# Barometer_revb.net
KiCad netlist of a schematic drawn in EAGLE
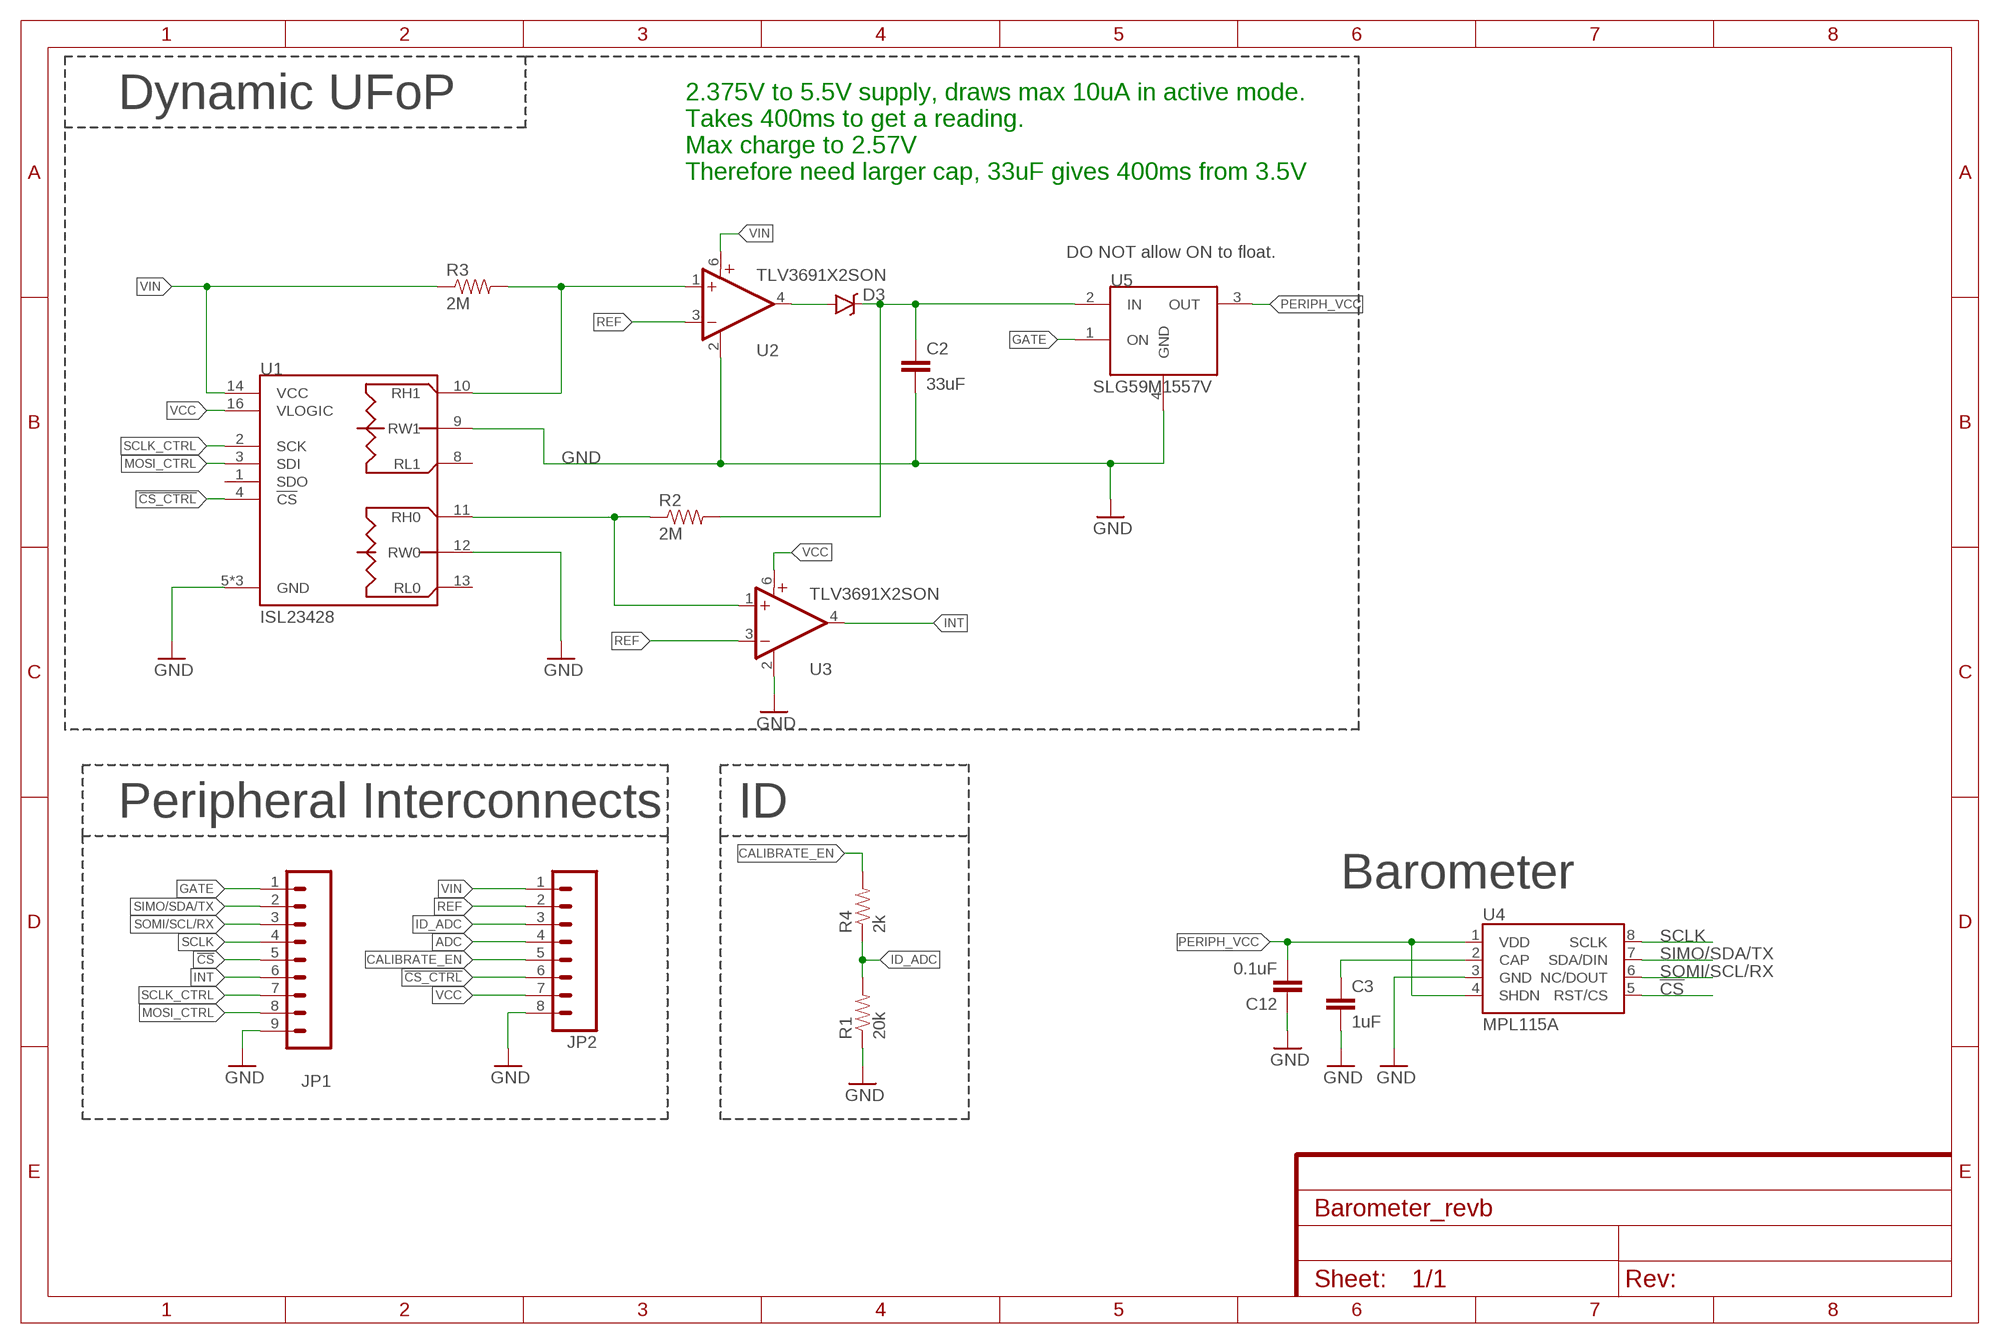
[diagram p0: schematic, sheet 1]

(export (version "E")
  (design (tool "Eeschema 10.0.6"))
  (components
    (comp (ref "C2")
      (value "33uF")
      (footprint "eagle-import:1206")
      (fields (field (name "MPN") "C3216X5R0J336M130AC "))
      (libsource (lib "eagle-import") (part "CAP1206"))
    )
    (comp (ref "C3")
      (value "1uF")
      (footprint "eagle-import:0402")
      (fields (field (name "MPN") "0402ZD105KAT2A"))
      (libsource (lib "eagle-import") (part "C-EU"))
    )
    (comp (ref "C12")
      (value "0.1uF")
      (footprint "eagle-import:0402")
      (fields (field (name "MPN") "0402YD104KAT2A"))
      (libsource (lib "eagle-import") (part "C-EU"))
    )
    (comp (ref "D3")
      (value "RB751")
      (footprint "eagle-import:SOD-523")
      (fields (field (name "MPN") "BAS40-02V-V-G-08"))
      (libsource (lib "eagle-import") (part "DIODE-SCHOTTKY-RB751"))
    )
    (comp (ref "JP1")
      (value "M091.27MM")
      (footprint "eagle-import:1X09-1.27MM")
      (fields (field (name "MPN") "GRPB091VWVN-RC "))
      (libsource (lib "eagle-import") (part "M091.27MM"))
    )
    (comp (ref "JP2")
      (value "M081.27MM")
      (footprint "eagle-import:1X08-1.27MM")
      (fields (field (name "MPN") "GRPB081VWVN-RC "))
      (libsource (lib "eagle-import") (part "M081.27MM"))
    )
    (comp (ref "R1")
      (value "20k")
      (footprint "eagle-import:0402")
      (fields (field (name "MPN") "ERJ-2RKF2002X"))
      (libsource (lib "eagle-import") (part "R-EU"))
    )
    (comp (ref "R2")
      (value "2M")
      (footprint "eagle-import:0402")
      (fields (field (name "MPN") "RC1005F205CS"))
      (libsource (lib "eagle-import") (part "R-EU"))
    )
    (comp (ref "R3")
      (value "2M")
      (footprint "eagle-import:0402")
      (fields (field (name "MPN") "RC1005F205CS"))
      (libsource (lib "eagle-import") (part "R-EU"))
    )
    (comp (ref "R4")
      (value "2k")
      (footprint "eagle-import:0402")
      (fields (field (name "MPN") "MCR01MRTF1202"))
      (libsource (lib "eagle-import") (part "R-EU"))
    )
    (comp (ref "U1")
      (value "ISL23428")
      (footprint "eagle-import:UTQFN-16")
      (fields (field (name "MPN") "ISL23428TFRUZ-T7A"))
      (libsource (lib "eagle-import") (part "ISL23428"))
    )
    (comp (ref "U2")
      (value "TLV3691X2SON")
      (footprint "eagle-import:X2SON")
      (fields (field (name "MPN") "TLV3691IDPFR"))
      (libsource (lib "eagle-import") (part "TLV3691X2SON"))
    )
    (comp (ref "U3")
      (value "TLV3691X2SON")
      (footprint "eagle-import:X2SON")
      (fields (field (name "MPN") "TLV3691IDPFR"))
      (libsource (lib "eagle-import") (part "TLV3691X2SON"))
    )
    (comp (ref "U4")
      (value "MPL115A")
      (footprint "eagle-import:LGA8")
      (fields (field (name "MPN") "MPL115A1"))
      (libsource (lib "eagle-import") (part "MPL115A"))
    )
    (comp (ref "U5")
      (value "SLG59M1557V")
      (footprint "eagle-import:4STDFN")
      (fields (field (name "MPN") "SLG59M1557V "))
      (libsource (lib "eagle-import") (part "SLG59M1557V"))
    )
  )
  (nets
    (net (code "1") (name "/~{CS_CTRL}") (class "Default")
      (node (ref "JP2") (pin "6") (pinfunction "6_6") (pintype "passive"))
      (node (ref "U1") (pin "4") (pinfunction "~{CS}_4") (pintype "bidirectional"))
    )
    (net (code "2") (name "/~{CS}") (class "Default")
      (node (ref "JP1") (pin "5") (pinfunction "5_5") (pintype "passive"))
      (node (ref "U4") (pin "5") (pinfunction "RST/CS_5") (pintype "bidirectional"))
    )
    (net (code "3") (name "ADC") (class "Default")
      (node (ref "JP2") (pin "4") (pinfunction "4_4") (pintype "passive"))
    )
    (net (code "4") (name "CALIBRATE_EN") (class "Default")
      (node (ref "JP2") (pin "5") (pinfunction "5_5") (pintype "passive"))
      (node (ref "R4") (pin "2") (pinfunction "2_2") (pintype "passive"))
    )
    (net (code "5") (name "GATE") (class "Default")
      (node (ref "JP1") (pin "1") (pinfunction "1_1") (pintype "passive"))
      (node (ref "U5") (pin "1") (pinfunction "ON_1") (pintype "bidirectional"))
    )
    (net (code "6") (name "GND") (class "Default")
      (node (ref "C12") (pin "1") (pinfunction "1_1") (pintype "passive"))
      (node (ref "C2") (pin "2") (pinfunction "2_2") (pintype "passive"))
      (node (ref "C3") (pin "2") (pinfunction "2_2") (pintype "passive"))
      (node (ref "JP1") (pin "9") (pinfunction "9_9") (pintype "passive"))
      (node (ref "JP2") (pin "8") (pinfunction "8_8") (pintype "passive"))
      (node (ref "R1") (pin "1") (pinfunction "1_1") (pintype "passive"))
      (node (ref "U1") (pin "12") (pinfunction "RW0_12") (pintype "bidirectional"))
      (node (ref "U1") (pin "15") (pinfunction "GND_15") (pintype "bidirectional"))
      (node (ref "U1") (pin "5") (pinfunction "GND_5") (pintype "bidirectional"))
      (node (ref "U1") (pin "6") (pinfunction "GND_6") (pintype "bidirectional"))
      (node (ref "U1") (pin "9") (pinfunction "RW1_9") (pintype "bidirectional"))
      (node (ref "U2") (pin "2") (pinfunction "GND_2") (pintype "power_in"))
      (node (ref "U3") (pin "2") (pinfunction "GND_2") (pintype "power_in"))
      (node (ref "U4") (pin "3") (pinfunction "GND_3") (pintype "bidirectional"))
      (node (ref "U5") (pin "4") (pinfunction "GND_4") (pintype "bidirectional"))
    )
    (net (code "7") (name "ID_ADC") (class "Default")
      (node (ref "JP2") (pin "3") (pinfunction "3_3") (pintype "passive"))
      (node (ref "R1") (pin "2") (pinfunction "2_2") (pintype "passive"))
      (node (ref "R4") (pin "1") (pinfunction "1_1") (pintype "passive"))
    )
    (net (code "8") (name "INT") (class "Default")
      (node (ref "JP1") (pin "6") (pinfunction "6_6") (pintype "passive"))
      (node (ref "U3") (pin "4") (pinfunction "OUT_4") (pintype "output"))
    )
    (net (code "9") (name "MOSI_CTRL") (class "Default")
      (node (ref "JP1") (pin "8") (pinfunction "8_8") (pintype "passive"))
      (node (ref "U1") (pin "3") (pinfunction "SDI_3") (pintype "bidirectional"))
    )
    (net (code "10") (name "Net-(U1-RH0)") (class "Default")
      (node (ref "R2") (pin "1") (pinfunction "1_1") (pintype "passive"))
      (node (ref "U1") (pin "11") (pinfunction "RH0_11") (pintype "bidirectional"))
      (node (ref "U3") (pin "1") (pinfunction "+IN_1") (pintype "input"))
    )
    (net (code "11") (name "Net-(U1-RH1)") (class "Default")
      (node (ref "R3") (pin "2") (pinfunction "2_2") (pintype "passive"))
      (node (ref "U1") (pin "10") (pinfunction "RH1_10") (pintype "bidirectional"))
      (node (ref "U2") (pin "1") (pinfunction "+IN_1") (pintype "input"))
    )
    (net (code "12") (name "Net-(U2-OUT)") (class "Default")
      (node (ref "D3") (pin "A") (pinfunction "A_A") (pintype "passive"))
      (node (ref "U2") (pin "4") (pinfunction "OUT_4") (pintype "output"))
    )
    (net (code "13") (name "Net-(U4-CAP)") (class "Default")
      (node (ref "C3") (pin "1") (pinfunction "1_1") (pintype "passive"))
      (node (ref "U4") (pin "2") (pinfunction "CAP_2") (pintype "bidirectional"))
    )
    (net (code "14") (name "Net-(U5-IN)") (class "Default")
      (node (ref "C2") (pin "1") (pinfunction "1_1") (pintype "passive"))
      (node (ref "D3") (pin "C") (pinfunction "C_C") (pintype "passive"))
      (node (ref "R2") (pin "2") (pinfunction "2_2") (pintype "passive"))
      (node (ref "U5") (pin "2") (pinfunction "IN_2") (pintype "bidirectional"))
    )
    (net (code "15") (name "PERIPH_VCC") (class "Default")
      (node (ref "C12") (pin "2") (pinfunction "2_2") (pintype "passive"))
      (node (ref "U4") (pin "1") (pinfunction "VDD_1") (pintype "bidirectional"))
      (node (ref "U4") (pin "4") (pinfunction "SHDN_4") (pintype "bidirectional"))
      (node (ref "U5") (pin "3") (pinfunction "OUT_3") (pintype "bidirectional"))
    )
    (net (code "16") (name "REF") (class "Default")
      (node (ref "JP2") (pin "2") (pinfunction "2_2") (pintype "passive"))
      (node (ref "U2") (pin "3") (pinfunction "-IN_3") (pintype "input"))
      (node (ref "U3") (pin "3") (pinfunction "-IN_3") (pintype "input"))
    )
    (net (code "17") (name "SCLK") (class "Default")
      (node (ref "JP1") (pin "4") (pinfunction "4_4") (pintype "passive"))
      (node (ref "U4") (pin "8") (pinfunction "SCLK_8") (pintype "bidirectional"))
    )
    (net (code "18") (name "SCLK_CTRL") (class "Default")
      (node (ref "JP1") (pin "7") (pinfunction "7_7") (pintype "passive"))
      (node (ref "U1") (pin "2") (pinfunction "SCK_2") (pintype "bidirectional"))
    )
    (net (code "19") (name "SIMO{slash}SDA{slash}TX") (class "Default")
      (node (ref "JP1") (pin "2") (pinfunction "2_2") (pintype "passive"))
      (node (ref "U4") (pin "7") (pinfunction "SDA/DIN_7") (pintype "bidirectional"))
    )
    (net (code "20") (name "SOMI{slash}SCL{slash}RX") (class "Default")
      (node (ref "JP1") (pin "3") (pinfunction "3_3") (pintype "passive"))
      (node (ref "U4") (pin "6") (pinfunction "NC/DOUT_6") (pintype "bidirectional"))
    )
    (net (code "21") (name "VCC") (class "Default")
      (node (ref "JP2") (pin "7") (pinfunction "7_7") (pintype "passive"))
      (node (ref "U1") (pin "16") (pinfunction "VLOGIC_16") (pintype "bidirectional"))
      (node (ref "U3") (pin "6") (pinfunction "V+_6") (pintype "power_in"))
    )
    (net (code "22") (name "VIN") (class "Default")
      (node (ref "JP2") (pin "1") (pinfunction "1_1") (pintype "passive"))
      (node (ref "R3") (pin "1") (pinfunction "1_1") (pintype "passive"))
      (node (ref "U1") (pin "14") (pinfunction "VCC_14") (pintype "bidirectional"))
      (node (ref "U2") (pin "6") (pinfunction "V+_6") (pintype "power_in"))
    )
    (net (code "23") (name "unconnected-(U1-RL0-Pad13)") (class "Default")
      (node (ref "U1") (pin "13") (pinfunction "RL0_13") (pintype "bidirectional"))
    )
    (net (code "24") (name "unconnected-(U1-RL1-Pad8)") (class "Default")
      (node (ref "U1") (pin "8") (pinfunction "RL1_8") (pintype "bidirectional"))
    )
    (net (code "25") (name "unconnected-(U1-SDO-Pad1)") (class "Default")
      (node (ref "U1") (pin "1") (pinfunction "SDO_1") (pintype "bidirectional"))
    )
  )
)
